# FPGA_CONFIG.net
KiCad netlist of a schematic drawn in Altium Designer
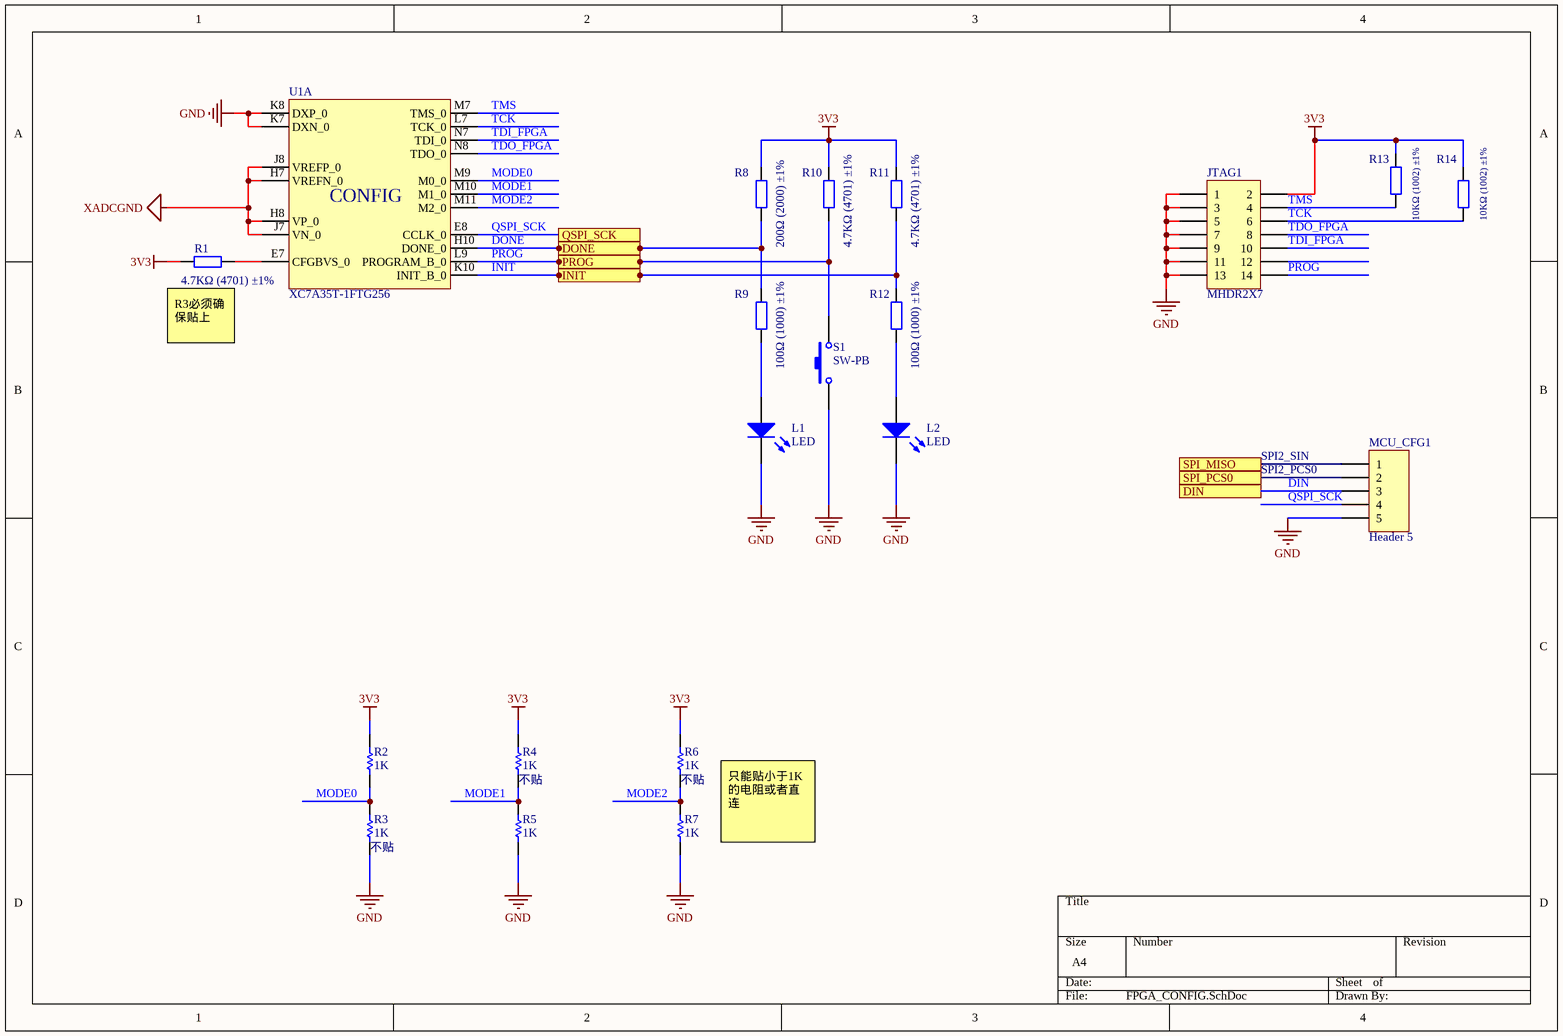
[diagram p0: FPGA_CONFIG.SchDoc]

(export (version "E")
  (design (tool "Eeschema 10.0.6"))
  (components
    (comp (ref "JTAG1")
      (value "MHDR2X7")
      (footprint "Hearder2 7X2")
      (description "Header, 7-Pin, Dual row")
      (fields (field (name "PUBLISHER") "Altium Limited"))
      (libsource (lib "Miscellaneous Connectors") (part "MHDR2X7"))
    )
    (comp (ref "L1") (value "LED") (footprint "1608[0603]") (libsource (lib "Sparks") (part "LED")))
    (comp (ref "L2") (value "LED") (footprint "1608[0603]") (libsource (lib "Sparks") (part "LED")))
    (comp (ref "MCU_CFG1")
      (value "Header 5")
      (footprint "MHDR1X5")
      (description "Header, 5-Pin")
      (fields (field (name "PUBLISHER") "Altium Limited"))
      (libsource (lib "Sparks") (part "Header 5"))
    )
    (comp (ref "R1")
      (value "4.7KΩ (4701) ±1%")
      (footprint "0402_R")
      (description "贴片电阻")
      (libsource (lib "RES") (part "0402 4.7KΩ (4701) 1%"))
    )
    (comp (ref "R2")
      (value "1K")
      (footprint "1608[0603]")
      (description "贴片电阻")
      (fields (field (name "Comment") "Res") (field (name "PUBLISHER") "Altium Limited"))
      (libsource (lib "Sparks") (part "Res"))
    )
    (comp (ref "R3")
      (value "不贴")
      (footprint "1608[0603]")
      (description "贴片电阻")
      (fields (field (name "ALTIUM_VALUE") "1K") (field (name "PUBLISHER") "Altium Limited"))
      (libsource (lib "Sparks") (part "Res"))
    )
    (comp (ref "R4")
      (value "不贴")
      (footprint "1608[0603]")
      (description "贴片电阻")
      (fields (field (name "ALTIUM_VALUE") "1K") (field (name "PUBLISHER") "Altium Limited"))
      (libsource (lib "Sparks") (part "Res"))
    )
    (comp (ref "R5")
      (value "1K")
      (footprint "1608[0603]")
      (description "贴片电阻")
      (fields (field (name "Comment") "Res") (field (name "PUBLISHER") "Altium Limited"))
      (libsource (lib "Sparks") (part "Res"))
    )
    (comp (ref "R6")
      (value "不贴")
      (footprint "1608[0603]")
      (description "贴片电阻")
      (fields (field (name "ALTIUM_VALUE") "1K") (field (name "PUBLISHER") "Altium Limited"))
      (libsource (lib "Sparks") (part "Res"))
    )
    (comp (ref "R7")
      (value "1K")
      (footprint "1608[0603]")
      (description "贴片电阻")
      (fields (field (name "Comment") "Res") (field (name "PUBLISHER") "Altium Limited"))
      (libsource (lib "Sparks") (part "Res"))
    )
    (comp (ref "R8")
      (value "200Ω (2000) ±1%")
      (footprint "0402_R")
      (description "贴片电阻")
      (libsource (lib "RES") (part "0402 200Ω (2000) 1%"))
    )
    (comp (ref "R9")
      (value "100Ω (1000) ±1%")
      (footprint "0402_R")
      (description "贴片电阻")
      (libsource (lib "RES") (part "0402 100Ω (1000) 1%"))
    )
    (comp (ref "R10")
      (value "4.7KΩ (4701) ±1%")
      (footprint "0402_R")
      (description "贴片电阻")
      (libsource (lib "") (part "0402 4.7KΩ (4701) 1%_1"))
    )
    (comp (ref "R11")
      (value "4.7KΩ (4701) ±1%")
      (footprint "0402_R")
      (description "贴片电阻")
      (libsource (lib "") (part "0402 4.7KΩ (4701) 1%_1"))
    )
    (comp (ref "R12")
      (value "100Ω (1000) ±1%")
      (footprint "0402_R")
      (description "贴片电阻")
      (libsource (lib "RES") (part "0402 100Ω (1000) 1%"))
    )
    (comp (ref "R13")
      (value "10KΩ (1002) ±1%")
      (footprint "0402_R")
      (description "贴片电阻")
      (libsource (lib "RES") (part "0402 10KΩ (1002) 1%"))
    )
    (comp (ref "R14")
      (value "10KΩ (1002) ±1%")
      (footprint "0402_R")
      (description "贴片电阻")
      (libsource (lib "RES") (part "0402 10KΩ (1002) 1%"))
    )
    (comp (ref "S1")
      (value "SW-PB")
      (footprint "key 3*4*2")
      (description "Switch")
      (fields (field (name "PUBLISHER") "Altium Limited"))
      (libsource (lib "Miscellaneous Devices") (part "SW-PB"))
    )
    (comp (ref "U1")
      (value "XC7A35T-1FTG256")
      (footprint "BGA100P9X9-81A")
      (libsource (lib "Schlib") (part "XC7A35T-1FTG256"))
    )
  )
  (nets
    (net (code "1") (name "/DIN") (class "Default")
      (node (ref "MCU_CFG1") (pin "3") (pinfunction "3_3") (pintype "passive"))
    )
    (net (code "2") (name "/DONE") (class "Default")
      (node (ref "R8") (pin "1") (pinfunction "1_1") (pintype "passive"))
      (node (ref "R9") (pin "2") (pinfunction "2_2") (pintype "passive"))
      (node (ref "U1") (pin "H10") (pinfunction "DONE_0_H10") (pintype "passive"))
    )
    (net (code "3") (name "/INIT") (class "Default")
      (node (ref "R11") (pin "1") (pinfunction "1_1") (pintype "passive"))
      (node (ref "R12") (pin "2") (pinfunction "2_2") (pintype "passive"))
      (node (ref "U1") (pin "K10") (pinfunction "INIT_B_0_K10") (pintype "passive"))
    )
    (net (code "4") (name "/MODE0") (class "Default")
      (node (ref "R2") (pin "1") (pinfunction "1_1") (pintype "passive"))
      (node (ref "R3") (pin "2") (pinfunction "2_2") (pintype "passive"))
      (node (ref "U1") (pin "M9") (pinfunction "M0_0_M9") (pintype "passive"))
    )
    (net (code "5") (name "/MODE1") (class "Default")
      (node (ref "R4") (pin "1") (pinfunction "1_1") (pintype "passive"))
      (node (ref "R5") (pin "2") (pinfunction "2_2") (pintype "passive"))
      (node (ref "U1") (pin "M10") (pinfunction "M1_0_M10") (pintype "passive"))
    )
    (net (code "6") (name "/MODE2") (class "Default")
      (node (ref "R6") (pin "1") (pinfunction "1_1") (pintype "passive"))
      (node (ref "R7") (pin "2") (pinfunction "2_2") (pintype "passive"))
      (node (ref "U1") (pin "M11") (pinfunction "M2_0_M11") (pintype "passive"))
    )
    (net (code "7") (name "/PROG") (class "Default")
      (node (ref "JTAG1") (pin "14") (pinfunction "14_14") (pintype "passive"))
      (node (ref "R10") (pin "1") (pinfunction "1_1") (pintype "passive"))
      (node (ref "S1") (pin "2") (pinfunction "2_2") (pintype "passive"))
      (node (ref "U1") (pin "L9") (pinfunction "PROGRAM_B_0_L9") (pintype "passive"))
    )
    (net (code "8") (name "/QSPI_SCK") (class "Default")
      (node (ref "MCU_CFG1") (pin "4") (pinfunction "4_4") (pintype "passive"))
      (node (ref "U1") (pin "E8") (pinfunction "CCLK_0_E8") (pintype "passive"))
    )
    (net (code "9") (name "/SPI2_PCS0") (class "Default")
      (node (ref "MCU_CFG1") (pin "2") (pinfunction "2_2") (pintype "passive"))
    )
    (net (code "10") (name "/SPI2_SIN") (class "Default")
      (node (ref "MCU_CFG1") (pin "1") (pinfunction "1_1") (pintype "passive"))
    )
    (net (code "11") (name "/TCK") (class "Default")
      (node (ref "JTAG1") (pin "6") (pinfunction "6_6") (pintype "passive"))
      (node (ref "R14") (pin "1") (pinfunction "1_1") (pintype "passive"))
      (node (ref "U1") (pin "L7") (pinfunction "TCK_0_L7") (pintype "passive"))
    )
    (net (code "12") (name "/TDI_FPGA") (class "Default")
      (node (ref "JTAG1") (pin "10") (pinfunction "10_10") (pintype "passive"))
      (node (ref "U1") (pin "N7") (pinfunction "TDI_0_N7") (pintype "passive"))
    )
    (net (code "13") (name "/TDO_FPGA") (class "Default")
      (node (ref "JTAG1") (pin "8") (pinfunction "8_8") (pintype "passive"))
      (node (ref "U1") (pin "N8") (pinfunction "TDO_0_N8") (pintype "passive"))
    )
    (net (code "14") (name "/TMS") (class "Default")
      (node (ref "JTAG1") (pin "4") (pinfunction "4_4") (pintype "passive"))
      (node (ref "R13") (pin "1") (pinfunction "1_1") (pintype "passive"))
      (node (ref "U1") (pin "M7") (pinfunction "TMS_0_M7") (pintype "passive"))
    )
    (net (code "15") (name "3V3") (class "Default")
      (node (ref "JTAG1") (pin "2") (pinfunction "2_2") (pintype "passive"))
      (node (ref "R1") (pin "1") (pinfunction "1_1") (pintype "passive"))
      (node (ref "R10") (pin "2") (pinfunction "2_2") (pintype "passive"))
      (node (ref "R11") (pin "2") (pinfunction "2_2") (pintype "passive"))
      (node (ref "R13") (pin "2") (pinfunction "2_2") (pintype "passive"))
      (node (ref "R14") (pin "2") (pinfunction "2_2") (pintype "passive"))
      (node (ref "R2") (pin "2") (pinfunction "2_2") (pintype "passive"))
      (node (ref "R4") (pin "2") (pinfunction "2_2") (pintype "passive"))
      (node (ref "R6") (pin "2") (pinfunction "2_2") (pintype "passive"))
      (node (ref "R8") (pin "2") (pinfunction "2_2") (pintype "passive"))
    )
    (net (code "16") (name "GND") (class "Default")
      (node (ref "JTAG1") (pin "1") (pinfunction "1_1") (pintype "passive"))
      (node (ref "JTAG1") (pin "11") (pinfunction "11_11") (pintype "passive"))
      (node (ref "JTAG1") (pin "13") (pinfunction "13_13") (pintype "passive"))
      (node (ref "JTAG1") (pin "3") (pinfunction "3_3") (pintype "passive"))
      (node (ref "JTAG1") (pin "5") (pinfunction "5_5") (pintype "passive"))
      (node (ref "JTAG1") (pin "7") (pinfunction "7_7") (pintype "passive"))
      (node (ref "JTAG1") (pin "9") (pinfunction "9_9") (pintype "passive"))
      (node (ref "L1") (pin "2") (pinfunction "K_2") (pintype "passive"))
      (node (ref "L2") (pin "2") (pinfunction "K_2") (pintype "passive"))
      (node (ref "MCU_CFG1") (pin "5") (pinfunction "5_5") (pintype "passive"))
      (node (ref "R3") (pin "1") (pinfunction "1_1") (pintype "passive"))
      (node (ref "R5") (pin "1") (pinfunction "1_1") (pintype "passive"))
      (node (ref "R7") (pin "1") (pinfunction "1_1") (pintype "passive"))
      (node (ref "S1") (pin "1") (pinfunction "1_1") (pintype "passive"))
      (node (ref "U1") (pin "K7") (pinfunction "DXN_0_K7") (pintype "passive"))
      (node (ref "U1") (pin "K8") (pinfunction "DXP_0_K8") (pintype "passive"))
    )
    (net (code "17") (name "Net-(L1-A)") (class "Default")
      (node (ref "L1") (pin "1") (pinfunction "A_1") (pintype "passive"))
      (node (ref "R9") (pin "1") (pinfunction "1_1") (pintype "passive"))
    )
    (net (code "18") (name "Net-(L2-A)") (class "Default")
      (node (ref "L2") (pin "1") (pinfunction "A_1") (pintype "passive"))
      (node (ref "R12") (pin "1") (pinfunction "1_1") (pintype "passive"))
    )
    (net (code "19") (name "Net-(U1A-CFGBVS_0)") (class "Default")
      (node (ref "R1") (pin "2") (pinfunction "2_2") (pintype "passive"))
      (node (ref "U1") (pin "E7") (pinfunction "CFGBVS_0_E7") (pintype "passive"))
    )
    (net (code "20") (name "XADCGND") (class "Default")
      (node (ref "U1") (pin "H7") (pinfunction "VREFN_0_H7") (pintype "passive"))
      (node (ref "U1") (pin "H8") (pinfunction "VP_0_H8") (pintype "passive"))
      (node (ref "U1") (pin "J7") (pinfunction "VN_0_J7") (pintype "passive"))
      (node (ref "U1") (pin "J8") (pinfunction "VREFP_0_J8") (pintype "passive"))
    )
    (net (code "21") (name "unconnected-(JTAG1-Pad12)") (class "Default")
      (node (ref "JTAG1") (pin "12") (pinfunction "12_12") (pintype "passive"))
    )
  )
)
